# AEMLION-R2.net
KiCad netlist of a schematic drawn in EAGLE
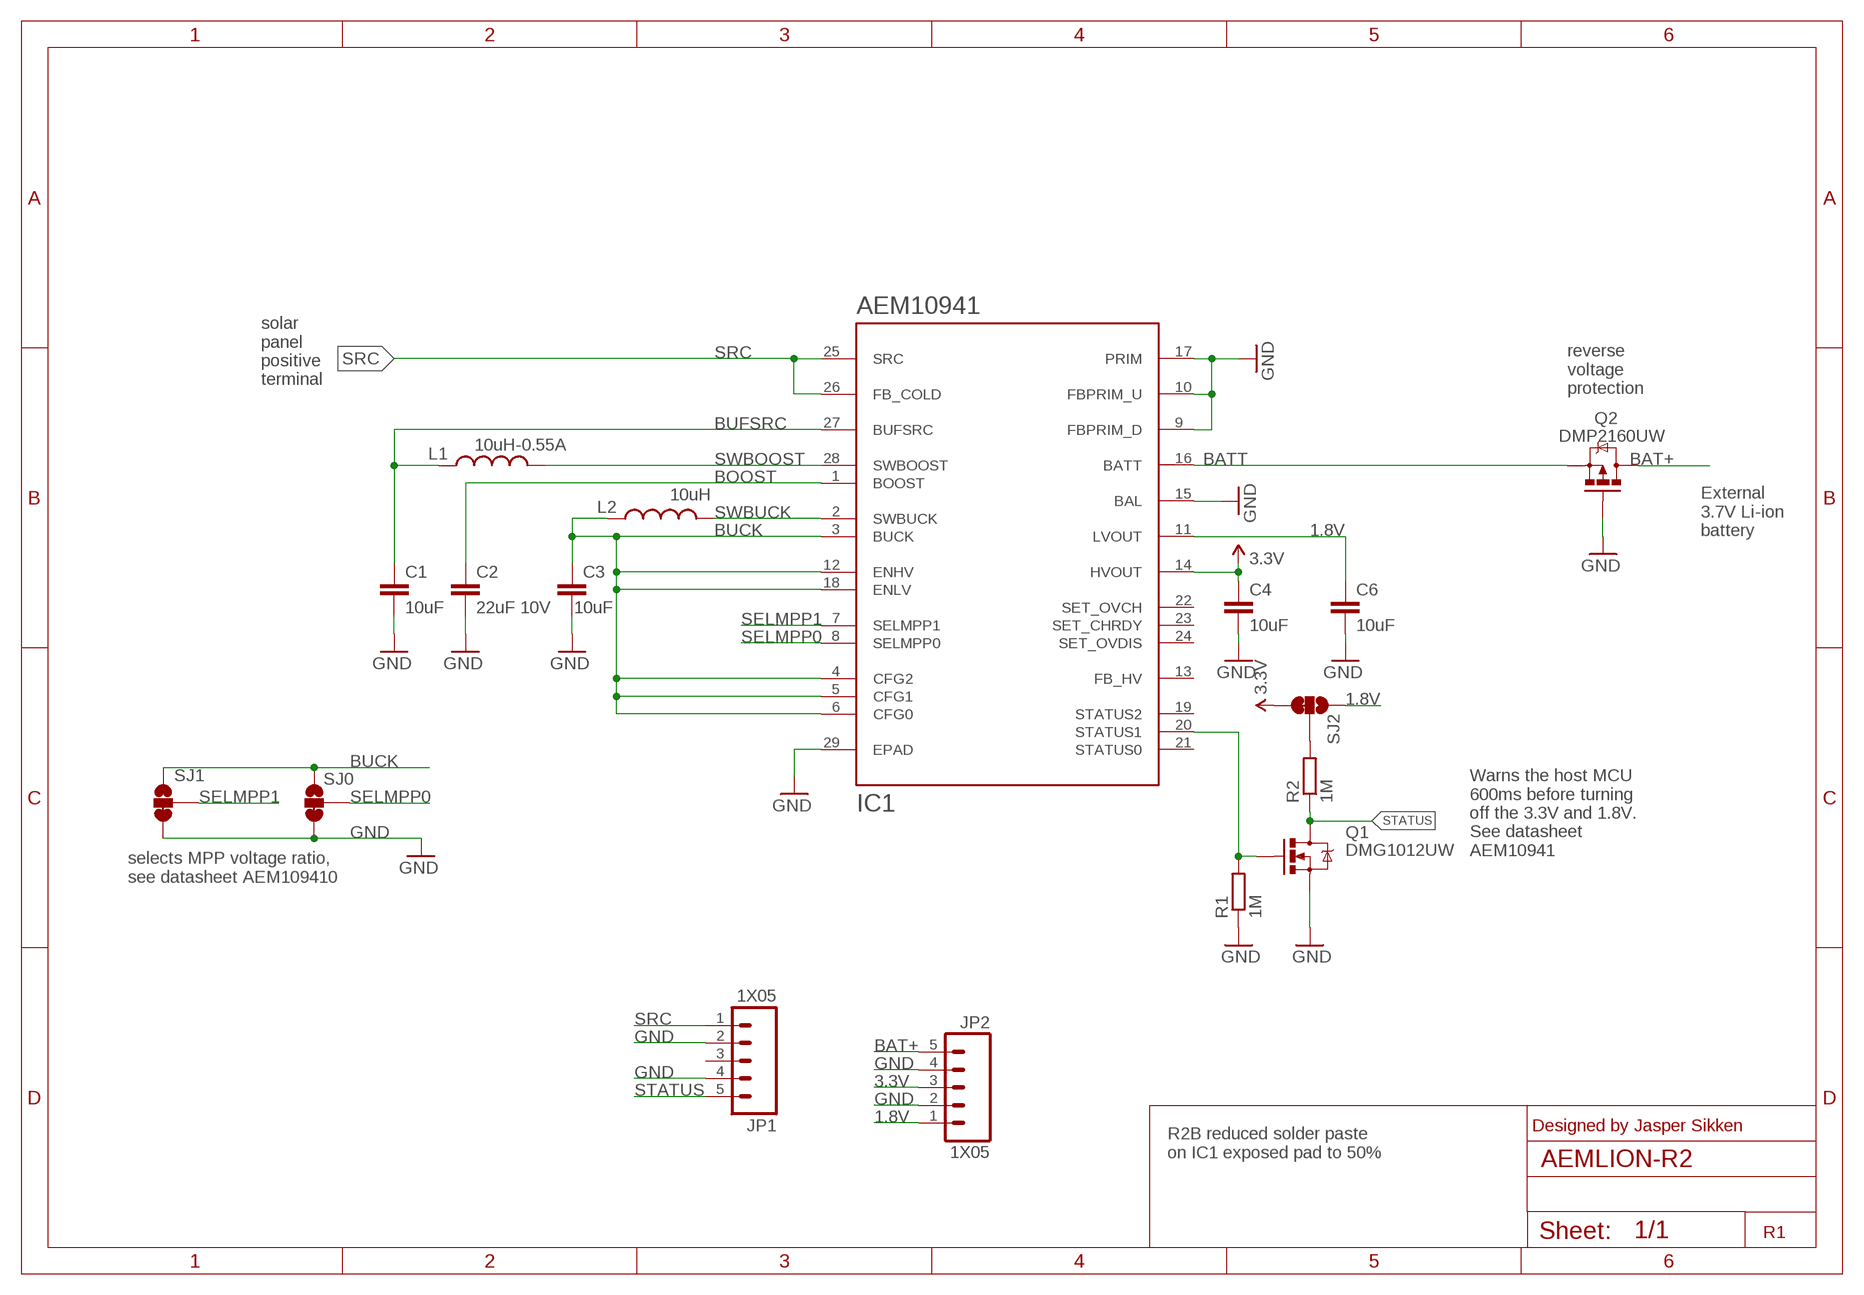
[diagram p0: schematic, sheet 1]

(export (version "E")
  (design (tool "Eeschema 10.0.6"))
  (components
    (comp (ref "C1")
      (value "10uF")
      (footprint "eagle-import:C0603")
      (fields (field (name "MF") "Taiyo Yuden") (field (name "MPN") "LMK107BBJ106MALT"))
      (libsource (lib "eagle-import") (part "C0603_10UF"))
    )
    (comp (ref "C2")
      (value "22uF 10V")
      (footprint "eagle-import:C0603")
      (fields (field (name "MF") "Murata") (field (name "MPN") "GRM188R61A226ME15D"))
      (libsource (lib "eagle-import") (part "C0603_22UF"))
    )
    (comp (ref "C3")
      (value "10uF")
      (footprint "eagle-import:C0603")
      (fields (field (name "MF") "Taiyo Yuden") (field (name "MPN") "LMK107BBJ106MALT"))
      (libsource (lib "eagle-import") (part "C0603_10UF"))
    )
    (comp (ref "C4")
      (value "10uF")
      (footprint "eagle-import:C0603")
      (fields (field (name "MF") "Taiyo Yuden") (field (name "MPN") "LMK107BBJ106MALT"))
      (libsource (lib "eagle-import") (part "C0603_10UF"))
    )
    (comp (ref "C6")
      (value "10uF")
      (footprint "eagle-import:C0603")
      (fields (field (name "MF") "Taiyo Yuden") (field (name "MPN") "LMK107BBJ106MALT"))
      (libsource (lib "eagle-import") (part "C0603_10UF"))
    )
    (comp (ref "IC1")
      (value "AEM10941")
      (footprint "eagle-import:QFN50P505X505X90-28")
      (fields (field (name "MF") "e-peas"))
      (libsource (lib "eagle-import") (part "AEM10941"))
    )
    (comp (ref "JP1")
      (value "1X05")
      (footprint "eagle-import:1X05_2.54MM_ROUND_NOSILK")
      (libsource (lib "eagle-import") (part "1X05"))
    )
    (comp (ref "JP2")
      (value "1X05")
      (footprint "eagle-import:1X05_2.54MM_ROUND_NOSILK")
      (libsource (lib "eagle-import") (part "1X05"))
    )
    (comp (ref "L1")
      (value "10uH-0.55A")
      (footprint "eagle-import:LPS4012")
      (fields (field (name "MF") "Coilcraft") (field (name "MPN") "LPS4012-103MRB"))
      (libsource (lib "eagle-import") (part "L3.9X3.9_10UH_0.55A"))
    )
    (comp (ref "L2")
      (value "10uH")
      (footprint "eagle-import:L0603")
      (fields (field (name "MF") "TDK") (field (name "MPN") "MLZ1608M100WT"))
      (libsource (lib "eagle-import") (part "L0603_10UH"))
    )
    (comp (ref "Q1")
      (value "DMG1012UW")
      (footprint "eagle-import:SOT323")
      (fields (field (name "MF") "Diodes") (field (name "MPN") "DMG1012UW-7"))
      (libsource (lib "eagle-import") (part "MOSFET-N-CHANNEL_DMG1012UW"))
    )
    (comp (ref "Q2")
      (value "DMP2160UW")
      (footprint "eagle-import:SOT323")
      (libsource (lib "eagle-import") (part "MOSFET-P-CHANNEL-DMP2160UW"))
    )
    (comp (ref "R1")
      (value "1M")
      (footprint "eagle-import:R0402")
      (fields (field (name "MF") "Walsin") (field (name "MPN") "WR04X1004FTL"))
      (libsource (lib "eagle-import") (part "R0402_1M"))
    )
    (comp (ref "R2")
      (value "1M")
      (footprint "eagle-import:R0402")
      (fields (field (name "MF") "Walsin") (field (name "MPN") "WR04X1004FTL"))
      (libsource (lib "eagle-import") (part "R0402_1M"))
    )
    (comp (ref "SJ0")
      (value "SOLDERJUMPER_3WAY_12SHORT3WAY")
      (footprint "eagle-import:SJ_3S_NC_0402")
      (libsource (lib "eagle-import") (part "SOLDERJUMPER_3WAY_12SHORT3WAY"))
    )
    (comp (ref "SJ1")
      (value "SOLDERJUMPER_3WAY_12SHORT3WAY")
      (footprint "eagle-import:SJ_3S_NC_0402")
      (libsource (lib "eagle-import") (part "SOLDERJUMPER_3WAY_12SHORT3WAY"))
    )
    (comp (ref "SJ2")
      (value "SOLDERJUMPER_3WAY_12SHORT3WAY")
      (footprint "eagle-import:SJ_3S_NC_0402")
      (libsource (lib "eagle-import") (part "SOLDERJUMPER_3WAY_12SHORT3WAY"))
    )
  )
  (nets
    (net (code "1") (name "/1.8V") (class "Default")
      (node (ref "C6") (pin "1") (pinfunction "1_1") (pintype "passive"))
      (node (ref "IC1") (pin "11") (pinfunction "LVOUT_11") (pintype "bidirectional"))
      (node (ref "JP2") (pin "1") (pinfunction "1_1") (pintype "passive"))
      (node (ref "SJ2") (pin "3") (pinfunction "3_3") (pintype "passive"))
    )
    (net (code "2") (name "/BAT+") (class "Default")
      (node (ref "JP2") (pin "5") (pinfunction "5_5") (pintype "passive"))
      (node (ref "Q2") (pin "3") (pinfunction "D_3") (pintype "passive"))
    )
    (net (code "3") (name "/BATT") (class "Default")
      (node (ref "IC1") (pin "16") (pinfunction "BATT_16") (pintype "bidirectional"))
      (node (ref "Q2") (pin "2") (pinfunction "S_2") (pintype "passive"))
    )
    (net (code "4") (name "/BOOST") (class "Default")
      (node (ref "C2") (pin "1") (pinfunction "1_1") (pintype "passive"))
      (node (ref "IC1") (pin "1") (pinfunction "BOOST_1") (pintype "bidirectional"))
    )
    (net (code "5") (name "/BUCK") (class "Default")
      (node (ref "C3") (pin "1") (pinfunction "1_1") (pintype "passive"))
      (node (ref "IC1") (pin "12") (pinfunction "ENHV_12") (pintype "bidirectional"))
      (node (ref "IC1") (pin "18") (pinfunction "ENLV_18") (pintype "bidirectional"))
      (node (ref "IC1") (pin "3") (pinfunction "BUCK_3") (pintype "bidirectional"))
      (node (ref "IC1") (pin "4") (pinfunction "CFG2_4") (pintype "bidirectional"))
      (node (ref "IC1") (pin "5") (pinfunction "CFG1_5") (pintype "bidirectional"))
      (node (ref "IC1") (pin "6") (pinfunction "CFG0_6") (pintype "bidirectional"))
      (node (ref "L2") (pin "1") (pinfunction "1_1") (pintype "passive"))
      (node (ref "SJ0") (pin "3") (pinfunction "3_3") (pintype "passive"))
      (node (ref "SJ1") (pin "3") (pinfunction "3_3") (pintype "passive"))
    )
    (net (code "6") (name "/BUFSRC") (class "Default")
      (node (ref "C1") (pin "1") (pinfunction "1_1") (pintype "passive"))
      (node (ref "IC1") (pin "27") (pinfunction "BUFSRC_27") (pintype "power_in"))
      (node (ref "L1") (pin "1") (pinfunction "1_1") (pintype "passive"))
    )
    (net (code "7") (name "/SELMPP0") (class "Default")
      (node (ref "IC1") (pin "8") (pinfunction "SELMPP0_8") (pintype "bidirectional"))
      (node (ref "SJ0") (pin "2") (pinfunction "2_2") (pintype "passive"))
    )
    (net (code "8") (name "/SELMPP1") (class "Default")
      (node (ref "IC1") (pin "7") (pinfunction "SELMPP1_7") (pintype "bidirectional"))
      (node (ref "SJ1") (pin "2") (pinfunction "2_2") (pintype "passive"))
    )
    (net (code "9") (name "/SWBOOST") (class "Default")
      (node (ref "IC1") (pin "28") (pinfunction "SWBOOST_28") (pintype "power_in"))
      (node (ref "L1") (pin "2") (pinfunction "2_2") (pintype "passive"))
    )
    (net (code "10") (name "/SWBUCK") (class "Default")
      (node (ref "IC1") (pin "2") (pinfunction "SWBUCK_2") (pintype "bidirectional"))
      (node (ref "L2") (pin "2") (pinfunction "2_2") (pintype "passive"))
    )
    (net (code "11") (name "3.3V") (class "Default")
      (node (ref "C4") (pin "1") (pinfunction "1_1") (pintype "passive"))
      (node (ref "IC1") (pin "14") (pinfunction "HVOUT_14") (pintype "bidirectional"))
      (node (ref "JP2") (pin "3") (pinfunction "3_3") (pintype "passive"))
      (node (ref "SJ2") (pin "1") (pinfunction "1_1") (pintype "passive"))
    )
    (net (code "12") (name "GND") (class "Default")
      (node (ref "C1") (pin "2") (pinfunction "2_2") (pintype "passive"))
      (node (ref "C2") (pin "2") (pinfunction "2_2") (pintype "passive"))
      (node (ref "C3") (pin "2") (pinfunction "2_2") (pintype "passive"))
      (node (ref "C4") (pin "2") (pinfunction "2_2") (pintype "passive"))
      (node (ref "C6") (pin "2") (pinfunction "2_2") (pintype "passive"))
      (node (ref "IC1") (pin "10") (pinfunction "FBPRIM_U_10") (pintype "bidirectional"))
      (node (ref "IC1") (pin "15") (pinfunction "BAL_15") (pintype "bidirectional"))
      (node (ref "IC1") (pin "17") (pinfunction "PRIM_17") (pintype "bidirectional"))
      (node (ref "IC1") (pin "29") (pinfunction "EPAD_29") (pintype "power_in"))
      (node (ref "IC1") (pin "9") (pinfunction "FBPRIM_D_9") (pintype "bidirectional"))
      (node (ref "JP1") (pin "2") (pinfunction "2_2") (pintype "passive"))
      (node (ref "JP1") (pin "4") (pinfunction "4_4") (pintype "passive"))
      (node (ref "JP2") (pin "2") (pinfunction "2_2") (pintype "passive"))
      (node (ref "JP2") (pin "4") (pinfunction "4_4") (pintype "passive"))
      (node (ref "Q1") (pin "2") (pinfunction "S_2") (pintype "passive"))
      (node (ref "Q2") (pin "1") (pinfunction "G_1") (pintype "passive"))
      (node (ref "R1") (pin "1") (pinfunction "1_1") (pintype "passive"))
      (node (ref "SJ0") (pin "1") (pinfunction "1_1") (pintype "passive"))
      (node (ref "SJ1") (pin "1") (pinfunction "1_1") (pintype "passive"))
    )
    (net (code "13") (name "Net-(IC1-STATUS1)") (class "Default")
      (node (ref "IC1") (pin "20") (pinfunction "STATUS1_20") (pintype "bidirectional"))
      (node (ref "Q1") (pin "1") (pinfunction "G_1") (pintype "passive"))
      (node (ref "R1") (pin "2") (pinfunction "2_2") (pintype "passive"))
    )
    (net (code "14") (name "Net-(R2-Pad2)") (class "Default")
      (node (ref "R2") (pin "2") (pinfunction "2_2") (pintype "passive"))
      (node (ref "SJ2") (pin "2") (pinfunction "2_2") (pintype "passive"))
    )
    (net (code "15") (name "SRC") (class "Default")
      (node (ref "IC1") (pin "25") (pinfunction "SRC_25") (pintype "power_in"))
      (node (ref "IC1") (pin "26") (pinfunction "FB_COLD_26") (pintype "input"))
      (node (ref "JP1") (pin "1") (pinfunction "1_1") (pintype "passive"))
    )
    (net (code "16") (name "STATUS") (class "Default")
      (node (ref "JP1") (pin "5") (pinfunction "5_5") (pintype "passive"))
      (node (ref "Q1") (pin "3") (pinfunction "D_3") (pintype "passive"))
      (node (ref "R2") (pin "1") (pinfunction "1_1") (pintype "passive"))
    )
    (net (code "17") (name "unconnected-(IC1-FB_HV-Pad13)") (class "Default")
      (node (ref "IC1") (pin "13") (pinfunction "FB_HV_13") (pintype "bidirectional"))
    )
    (net (code "18") (name "unconnected-(IC1-SET_CHRDY-Pad23)") (class "Default")
      (node (ref "IC1") (pin "23") (pinfunction "SET_CHRDY_23") (pintype "bidirectional"))
    )
    (net (code "19") (name "unconnected-(IC1-SET_OVCH-Pad22)") (class "Default")
      (node (ref "IC1") (pin "22") (pinfunction "SET_OVCH_22") (pintype "bidirectional"))
    )
    (net (code "20") (name "unconnected-(IC1-SET_OVDIS-Pad24)") (class "Default")
      (node (ref "IC1") (pin "24") (pinfunction "SET_OVDIS_24") (pintype "bidirectional"))
    )
    (net (code "21") (name "unconnected-(IC1-STATUS0-Pad21)") (class "Default")
      (node (ref "IC1") (pin "21") (pinfunction "STATUS0_21") (pintype "bidirectional"))
    )
    (net (code "22") (name "unconnected-(IC1-STATUS2-Pad19)") (class "Default")
      (node (ref "IC1") (pin "19") (pinfunction "STATUS2_19") (pintype "bidirectional"))
    )
    (net (code "23") (name "unconnected-(JP1-Pad3)") (class "Default")
      (node (ref "JP1") (pin "3") (pinfunction "3_3") (pintype "passive"))
    )
  )
)
